# ETH_on_RS485_Node_Example_TOP.net
KiCad netlist of a schematic drawn in Altium Designer
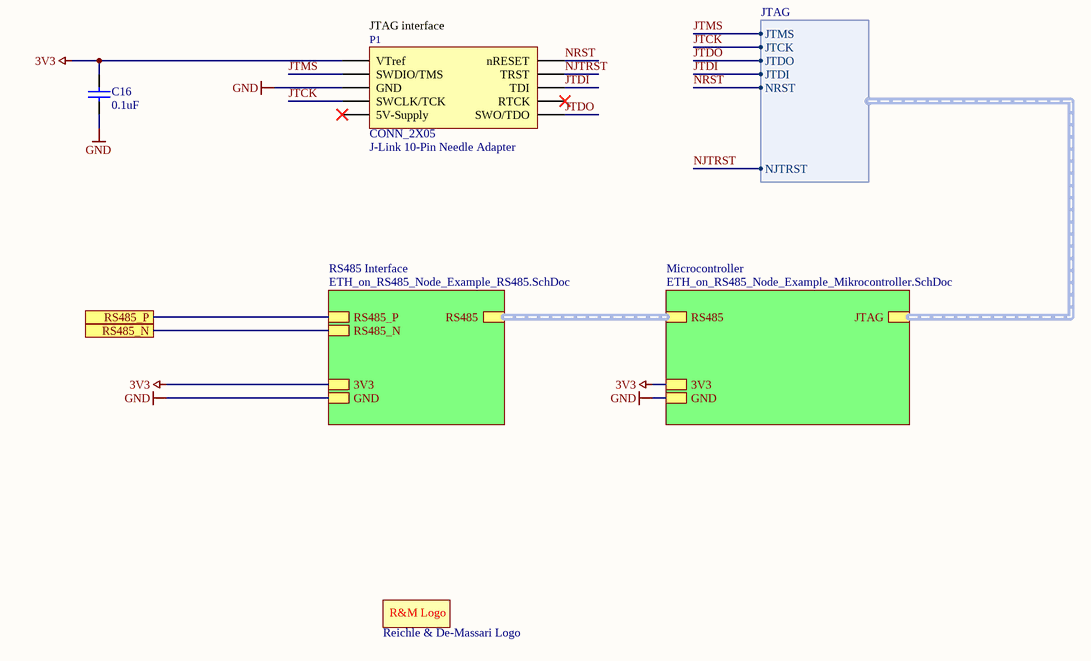
[diagram p0: ETH_on_RS485_Node_Example_TOP.SchDoc]

(export (version "E")
  (design (tool "Eeschema 10.0.6"))
  (components
    (comp (ref "1")
      (value "Reichle & De-Massari Logo")
      (footprint "SYMBOL_R&M")
      (libsource (lib "RDM_Altium_Library") (part "SYMBOL_R&M"))
    )
    (comp (ref "C16")
      (value "0.1uF")
      (footprint "Ceramic Capacitor 0402 EIA")
      (description "SMD/SMT WCAP-CSGP 0.1uF 0402 20% 10V MLCC")
      (fields (field (name "TOLERANCE") "20%") (field (name "VOLTAGE") "10VDC"))
      (libsource (lib "RDM_Altium_Library") (part "Cap_0.1uF_0402"))
    )
    (comp (ref "P1")
      (value "CONN_2X05")
      (footprint "CONN_2X05_SEGGER")
      (description "J-Link 10-Pin Needle Adapter")
      (fields
        (field (name "MANUFACTURER") "Samtec")
        (field (name "MANUFACTURER PARTNR") "J-Link 10-Pin Needle Adapter")
      )
      (libsource (lib "RDM_Altium_Library") (part "CONN_2X05_SEGGER"))
    )
  )
  (nets
    (net (code "2") (name "/JTCK") (class "Default")
      (node (ref "P1") (pin "4") (pinfunction "SWCLK/TCK_4") (pintype "passive"))
    )
    (net (code "3") (name "/JTDI") (class "Default")
      (node (ref "P1") (pin "8") (pinfunction "TDI_8") (pintype "passive"))
    )
    (net (code "4") (name "/JTDO") (class "Default")
      (node (ref "P1") (pin "6") (pinfunction "SWO/TDO_6") (pintype "passive"))
    )
    (net (code "5") (name "/JTMS") (class "Default")
      (node (ref "P1") (pin "2") (pinfunction "SWDIO/TMS_2") (pintype "passive"))
    )
    (net (code "6") (name "/NJTRST") (class "Default")
      (node (ref "P1") (pin "9") (pinfunction "TRST_9") (pintype "passive"))
    )
    (net (code "7") (name "/NRST") (class "Default")
      (node (ref "P1") (pin "10") (pinfunction "nRESET_10") (pintype "passive"))
    )
    (net (code "12") (name "3V3") (class "Default")
      (node (ref "C16") (pin "2") (pinfunction "2_2") (pintype "passive"))
      (node (ref "P1") (pin "1") (pinfunction "VTref_1") (pintype "passive"))
    )
    (net (code "13") (name "GND") (class "Default")
      (node (ref "C16") (pin "1") (pinfunction "1_1") (pintype "passive"))
      (node (ref "P1") (pin "3") (pinfunction "GND_3") (pintype "passive"))
    )
    (net (code "14") (name "unconnected-(P1-5V-Supply-Pad5)") (class "Default")
      (node (ref "P1") (pin "5") (pinfunction "5V-Supply_5") (pintype "passive+no_connect"))
    )
    (net (code "15") (name "unconnected-(P1-RTCK-Pad7)") (class "Default")
      (node (ref "P1") (pin "7") (pinfunction "RTCK_7") (pintype "passive+no_connect"))
    )
  )
)
